# shema_01.net
KiCad netlist of a schematic drawn in EAGLE
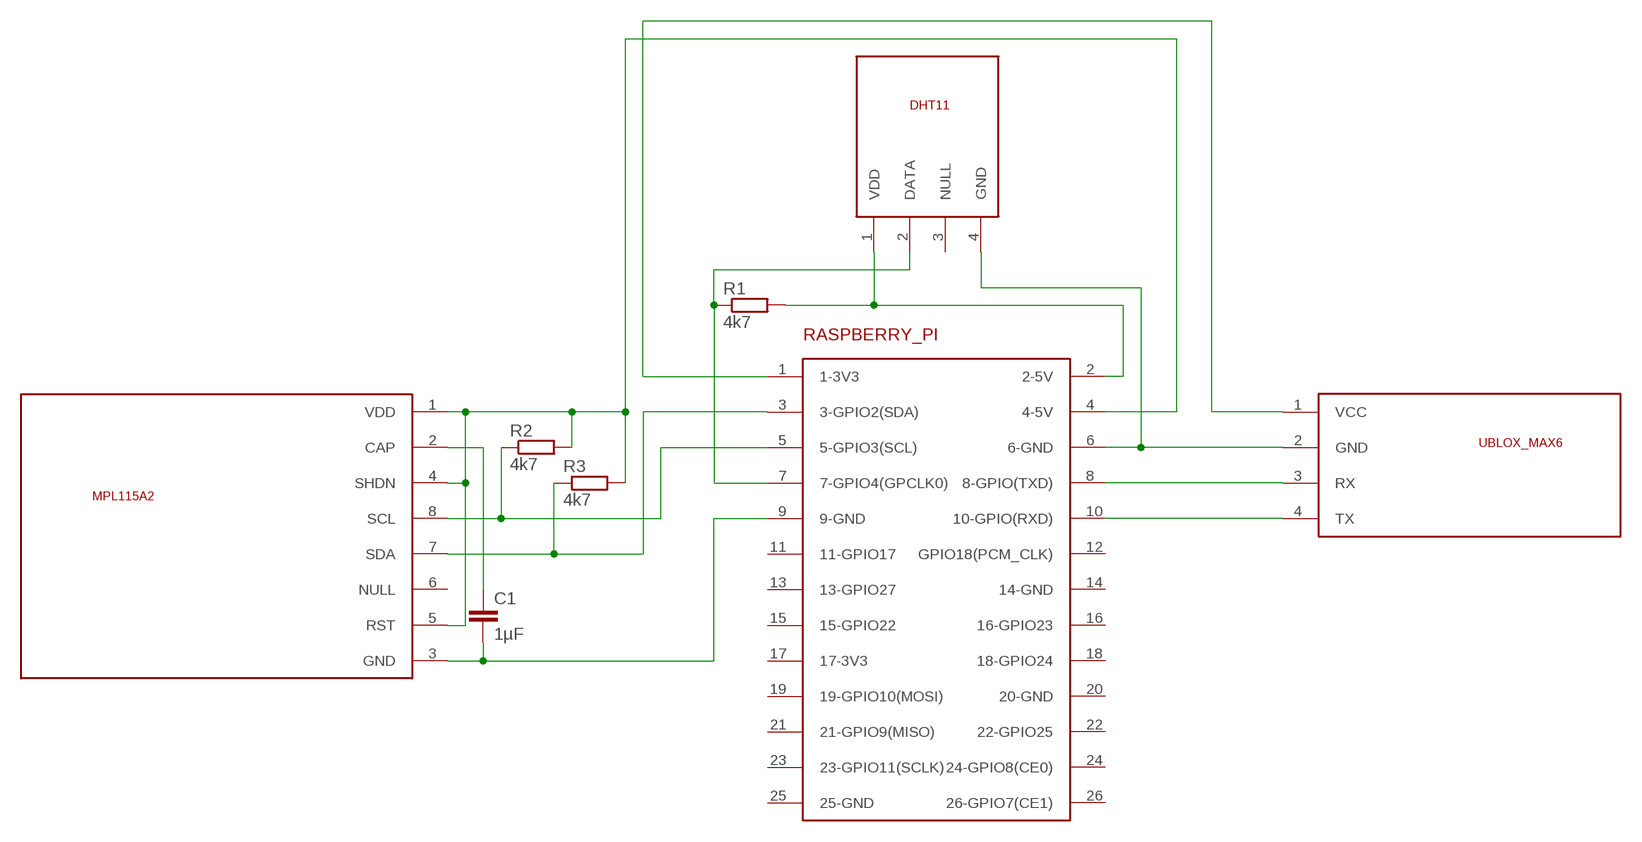
[diagram p0: schematic, sheet 1]

(export (version "E")
  (design (tool "Eeschema 10.0.6"))
  (components
    (comp (ref "C1")
      (value "1µF")
      (footprint "eagle-import:C2.5-6")
      (libsource (lib "eagle-import") (part "C2.5/6"))
    )
    (comp (ref "DHT11")
      (value "DHT11")
      (footprint "eagle-import:DHT11")
      (libsource (lib "eagle-import") (part "DHT11"))
    )
    (comp (ref "MPL115A2")
      (value "PRITISK")
      (footprint "eagle-import:PRITISK")
      (libsource (lib "eagle-import") (part "PRITISK"))
    )
    (comp (ref "R1")
      (value "4k7")
      (footprint "eagle-import:0207_12")
      (libsource (lib "eagle-import") (part "R-EU_0207/12"))
    )
    (comp (ref "R2")
      (value "4k7")
      (footprint "eagle-import:0309_10")
      (libsource (lib "eagle-import") (part "resistor_R-EU_0309/10"))
    )
    (comp (ref "R3")
      (value "4k7")
      (footprint "eagle-import:0309_10")
      (libsource (lib "eagle-import") (part "resistor_R-EU_0309/10"))
    )
    (comp (ref "RASPBERRY_PI")
      (value "RASPBERRY-PI")
      (footprint "eagle-import:RASPBERRY-PI")
      (libsource (lib "eagle-import") (part "RASPBERRY-PI"))
    )
    (comp (ref "UBLOX_MAX6")
      (value "GPS")
      (footprint "eagle-import:GPS")
      (libsource (lib "eagle-import") (part "GPS"))
    )
  )
  (nets
    (net (code "1") (name "Net-(DHT11-DATA)") (class "Default")
      (node (ref "DHT11") (pin "2") (pinfunction "DATA_2") (pintype "passive"))
      (node (ref "R1") (pin "1") (pinfunction "1_1") (pintype "passive"))
      (node (ref "RASPBERRY_PI") (pin "7") (pinfunction "7-GPIO4(GPCLK0)_7") (pintype "bidirectional"))
    )
    (net (code "2") (name "Net-(DHT11-GND)") (class "Default")
      (node (ref "DHT11") (pin "4") (pinfunction "GND_4") (pintype "passive"))
      (node (ref "RASPBERRY_PI") (pin "6") (pinfunction "6-GND_6") (pintype "bidirectional"))
      (node (ref "UBLOX_MAX6") (pin "2") (pinfunction "GND_2") (pintype "bidirectional"))
    )
    (net (code "3") (name "Net-(DHT11-VDD)") (class "Default")
      (node (ref "DHT11") (pin "1") (pinfunction "VDD_1") (pintype "passive"))
      (node (ref "R1") (pin "2") (pinfunction "2_2") (pintype "passive"))
      (node (ref "RASPBERRY_PI") (pin "2") (pinfunction "2-5V_2") (pintype "bidirectional"))
    )
    (net (code "4") (name "Net-(MPL115A2-CAP)") (class "Default")
      (node (ref "C1") (pin "1") (pinfunction "1_1") (pintype "passive"))
      (node (ref "MPL115A2") (pin "2") (pinfunction "CAP_2") (pintype "bidirectional"))
    )
    (net (code "5") (name "Net-(MPL115A2-GND)") (class "Default")
      (node (ref "C1") (pin "2") (pinfunction "2_2") (pintype "passive"))
      (node (ref "MPL115A2") (pin "3") (pinfunction "GND_3") (pintype "bidirectional"))
      (node (ref "RASPBERRY_PI") (pin "9") (pinfunction "9-GND_9") (pintype "bidirectional"))
    )
    (net (code "6") (name "Net-(MPL115A2-RST)") (class "Default")
      (node (ref "MPL115A2") (pin "1") (pinfunction "VDD_1") (pintype "bidirectional"))
      (node (ref "MPL115A2") (pin "4") (pinfunction "SHDN_4") (pintype "bidirectional"))
      (node (ref "MPL115A2") (pin "5") (pinfunction "RST_5") (pintype "bidirectional"))
      (node (ref "R2") (pin "2") (pinfunction "2_2") (pintype "passive"))
      (node (ref "R3") (pin "2") (pinfunction "2_2") (pintype "passive"))
      (node (ref "RASPBERRY_PI") (pin "4") (pinfunction "4-5V_4") (pintype "bidirectional"))
    )
    (net (code "7") (name "Net-(MPL115A2-SCL)") (class "Default")
      (node (ref "MPL115A2") (pin "8") (pinfunction "SCL_8") (pintype "bidirectional"))
      (node (ref "R2") (pin "1") (pinfunction "1_1") (pintype "passive"))
      (node (ref "RASPBERRY_PI") (pin "5") (pinfunction "5-GPIO3(SCL)_5") (pintype "bidirectional"))
    )
    (net (code "8") (name "Net-(MPL115A2-SDA)") (class "Default")
      (node (ref "MPL115A2") (pin "7") (pinfunction "SDA_7") (pintype "bidirectional"))
      (node (ref "R3") (pin "1") (pinfunction "1_1") (pintype "passive"))
      (node (ref "RASPBERRY_PI") (pin "3") (pinfunction "3-GPIO2(SDA)_3") (pintype "bidirectional"))
    )
    (net (code "9") (name "Net-(RASPBERRY_PI-1-3V3)") (class "Default")
      (node (ref "RASPBERRY_PI") (pin "1") (pinfunction "1-3V3_1") (pintype "bidirectional"))
      (node (ref "UBLOX_MAX6") (pin "1") (pinfunction "VCC_1") (pintype "bidirectional"))
    )
    (net (code "10") (name "Net-(RASPBERRY_PI-8-GPIO(TXD))") (class "Default")
      (node (ref "RASPBERRY_PI") (pin "8") (pinfunction "8-GPIO(TXD)_8") (pintype "bidirectional"))
      (node (ref "UBLOX_MAX6") (pin "3") (pinfunction "RX_3") (pintype "bidirectional"))
    )
    (net (code "11") (name "Net-(RASPBERRY_PI-10-GPIO(RXD))") (class "Default")
      (node (ref "RASPBERRY_PI") (pin "10") (pinfunction "10-GPIO(RXD)_10") (pintype "bidirectional"))
      (node (ref "UBLOX_MAX6") (pin "4") (pinfunction "TX_4") (pintype "bidirectional"))
    )
    (net (code "12") (name "unconnected-(DHT11-NULL-Pad3)") (class "Default")
      (node (ref "DHT11") (pin "3") (pinfunction "NULL_3") (pintype "passive"))
    )
    (net (code "13") (name "unconnected-(MPL115A2-NULL-Pad6)") (class "Default")
      (node (ref "MPL115A2") (pin "6") (pinfunction "NULL_6") (pintype "bidirectional"))
    )
    (net (code "14") (name "unconnected-(RASPBERRY_PI-11-GPIO17-Pad11)") (class "Default")
      (node (ref "RASPBERRY_PI") (pin "11") (pinfunction "11-GPIO17_11") (pintype "bidirectional"))
    )
    (net (code "15") (name "unconnected-(RASPBERRY_PI-13-GPIO27-Pad13)") (class "Default")
      (node (ref "RASPBERRY_PI") (pin "13") (pinfunction "13-GPIO27_13") (pintype "bidirectional"))
    )
    (net (code "16") (name "unconnected-(RASPBERRY_PI-14-GND-Pad14)") (class "Default")
      (node (ref "RASPBERRY_PI") (pin "14") (pinfunction "14-GND_14") (pintype "bidirectional"))
    )
    (net (code "17") (name "unconnected-(RASPBERRY_PI-15-GPIO22-Pad15)") (class "Default")
      (node (ref "RASPBERRY_PI") (pin "15") (pinfunction "15-GPIO22_15") (pintype "bidirectional"))
    )
    (net (code "18") (name "unconnected-(RASPBERRY_PI-16-GPIO23-Pad16)") (class "Default")
      (node (ref "RASPBERRY_PI") (pin "16") (pinfunction "16-GPIO23_16") (pintype "bidirectional"))
    )
    (net (code "19") (name "unconnected-(RASPBERRY_PI-17-3V3-Pad17)") (class "Default")
      (node (ref "RASPBERRY_PI") (pin "17") (pinfunction "17-3V3_17") (pintype "bidirectional"))
    )
    (net (code "20") (name "unconnected-(RASPBERRY_PI-18-GPIO24-Pad18)") (class "Default")
      (node (ref "RASPBERRY_PI") (pin "18") (pinfunction "18-GPIO24_18") (pintype "bidirectional"))
    )
    (net (code "21") (name "unconnected-(RASPBERRY_PI-19-GPIO10(MOSI)-Pad19)") (class "Default")
      (node (ref "RASPBERRY_PI") (pin "19") (pinfunction "19-GPIO10(MOSI)_19") (pintype "bidirectional"))
    )
    (net (code "22") (name "unconnected-(RASPBERRY_PI-20-GND-Pad20)") (class "Default")
      (node (ref "RASPBERRY_PI") (pin "20") (pinfunction "20-GND_20") (pintype "bidirectional"))
    )
    (net (code "23") (name "unconnected-(RASPBERRY_PI-21-GPIO9(MISO)-Pad21)") (class "Default")
      (node (ref "RASPBERRY_PI") (pin "21") (pinfunction "21-GPIO9(MISO)_21") (pintype "bidirectional"))
    )
    (net (code "24") (name "unconnected-(RASPBERRY_PI-22-GPIO25-Pad22)") (class "Default")
      (node (ref "RASPBERRY_PI") (pin "22") (pinfunction "22-GPIO25_22") (pintype "bidirectional"))
    )
    (net (code "25") (name "unconnected-(RASPBERRY_PI-23-GPIO11(SCLK)-Pad23)") (class "Default")
      (node (ref "RASPBERRY_PI") (pin "23") (pinfunction "23-GPIO11(SCLK)_23") (pintype "bidirectional"))
    )
    (net (code "26") (name "unconnected-(RASPBERRY_PI-24-GPIO8(CE0)-Pad24)") (class "Default")
      (node (ref "RASPBERRY_PI") (pin "24") (pinfunction "24-GPIO8(CE0)_24") (pintype "bidirectional"))
    )
    (net (code "27") (name "unconnected-(RASPBERRY_PI-25-GND-Pad25)") (class "Default")
      (node (ref "RASPBERRY_PI") (pin "25") (pinfunction "25-GND_25") (pintype "bidirectional"))
    )
    (net (code "28") (name "unconnected-(RASPBERRY_PI-26-GPIO7(CE1)-Pad26)") (class "Default")
      (node (ref "RASPBERRY_PI") (pin "26") (pinfunction "26-GPIO7(CE1)_26") (pintype "bidirectional"))
    )
    (net (code "29") (name "unconnected-(RASPBERRY_PI-GPIO18(PCM_CLK)-Pad12)") (class "Default")
      (node (ref "RASPBERRY_PI") (pin "12") (pinfunction "GPIO18(PCM_CLK)_12") (pintype "bidirectional"))
    )
  )
)
